# Controller.net
KiCad netlist of a schematic drawn in EAGLE
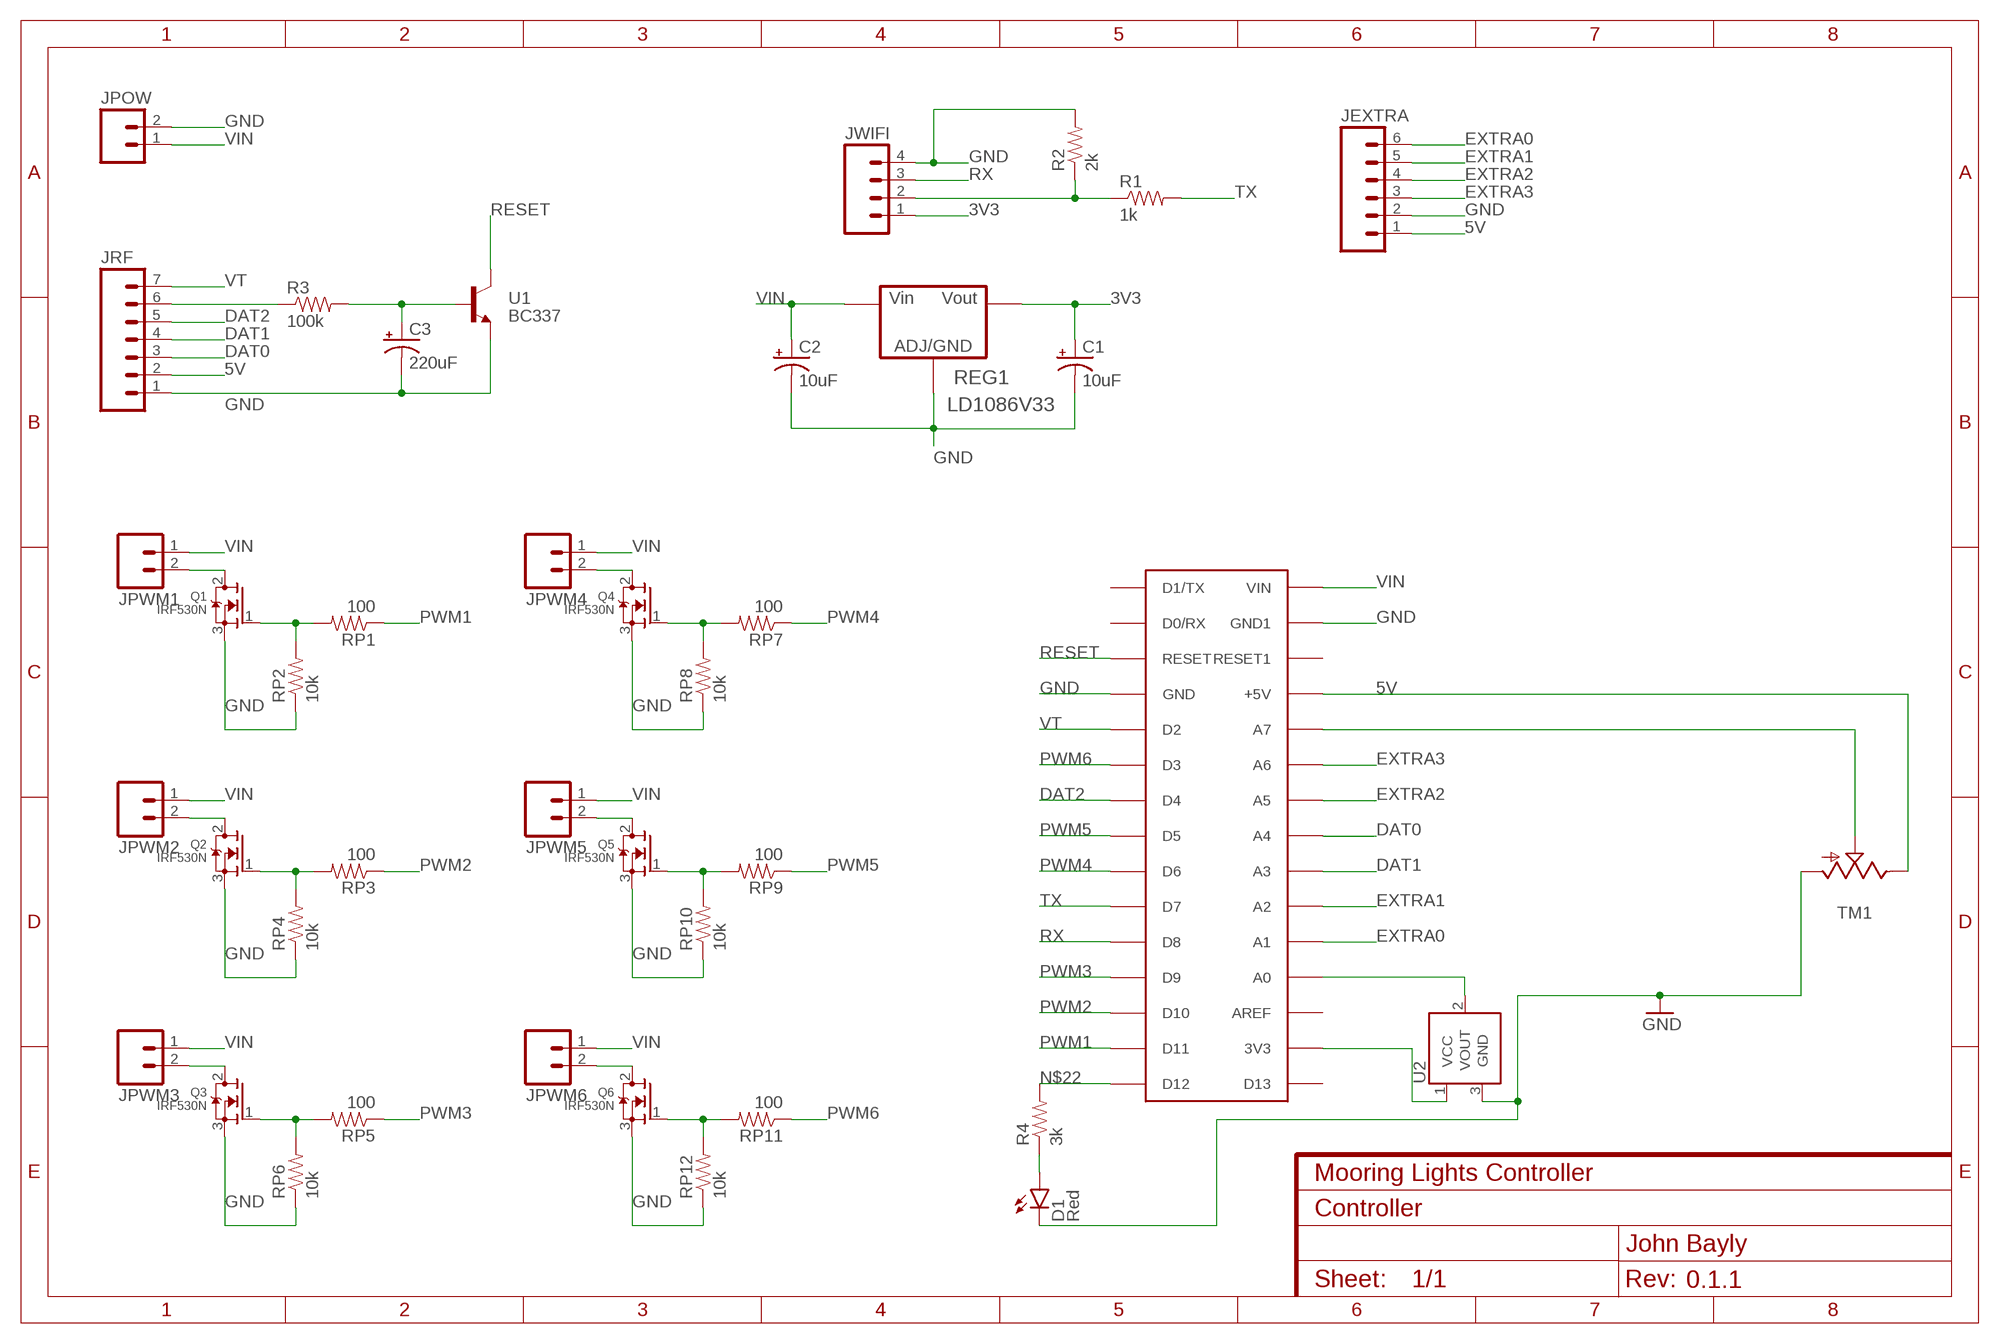
[diagram p0: schematic, sheet 1]

(export (version "E")
  (design (tool "Eeschema 10.0.6"))
  (components
    (comp (ref "C1")
      (value "10uF")
      (footprint "eagle-import:CPOL-RADIAL-10UF-25V")
      (libsource (lib "eagle-import") (part "10UF-25V-20%(PTH)"))
    )
    (comp (ref "C2")
      (value "10uF")
      (footprint "eagle-import:CPOL-RADIAL-10UF-25V")
      (libsource (lib "eagle-import") (part "10UF-25V-20%(PTH)"))
    )
    (comp (ref "C3")
      (value "220uF")
      (footprint "eagle-import:CPOL-RADIAL-100UF-25V")
      (libsource (lib "eagle-import") (part "100UF-25V-20%(PTH)"))
    )
    (comp (ref "D1")
      (value "Red")
      (footprint "eagle-import:LED5MM")
      (libsource (lib "eagle-import") (part "LED5MM"))
    )
    (comp (ref "JEXTRA")
      (value "M06SILK_FEMALE_PTH")
      (footprint "eagle-import:1X06")
      (libsource (lib "eagle-import") (part "M06SILK_FEMALE_PTH"))
    )
    (comp (ref "JPOW")
      (value "M025MM")
      (footprint "eagle-import:SCREWTERMINAL-5MM-2")
      (libsource (lib "eagle-import") (part "M025MM"))
    )
    (comp (ref "JPWM1")
      (value "M025MM")
      (footprint "eagle-import:SCREWTERMINAL-5MM-2")
      (libsource (lib "eagle-import") (part "M025MM"))
    )
    (comp (ref "JPWM2")
      (value "M025MM")
      (footprint "eagle-import:SCREWTERMINAL-5MM-2")
      (libsource (lib "eagle-import") (part "M025MM"))
    )
    (comp (ref "JPWM3")
      (value "M025MM")
      (footprint "eagle-import:SCREWTERMINAL-5MM-2")
      (libsource (lib "eagle-import") (part "M025MM"))
    )
    (comp (ref "JPWM4")
      (value "M025MM")
      (footprint "eagle-import:SCREWTERMINAL-5MM-2")
      (libsource (lib "eagle-import") (part "M025MM"))
    )
    (comp (ref "JPWM5")
      (value "M025MM")
      (footprint "eagle-import:SCREWTERMINAL-5MM-2")
      (libsource (lib "eagle-import") (part "M025MM"))
    )
    (comp (ref "JPWM6")
      (value "M025MM")
      (footprint "eagle-import:SCREWTERMINAL-5MM-2")
      (libsource (lib "eagle-import") (part "M025MM"))
    )
    (comp (ref "JRF")
      (value "M07")
      (footprint "eagle-import:1X07")
      (libsource (lib "eagle-import") (part "M07"))
    )
    (comp (ref "JWIFI")
      (value "M04PTH")
      (footprint "eagle-import:1X04")
      (libsource (lib "eagle-import") (part "M04PTH"))
    )
    (comp (ref "NANO")
      (value "ARDUINONANONO-MOUNT")
      (footprint "eagle-import:PDIP-32-NO-MOUNT")
      (libsource (lib "eagle-import") (part "ARDUINONANONO-MOUNT"))
    )
    (comp (ref "Q1")
      (value "IRF530N")
      (footprint "eagle-import:TO220V")
      (libsource (lib "eagle-import") (part "MOSFET-NGDS_TO220V"))
    )
    (comp (ref "Q2")
      (value "IRF530N")
      (footprint "eagle-import:TO220V")
      (libsource (lib "eagle-import") (part "MOSFET-NGDS_TO220V"))
    )
    (comp (ref "Q3")
      (value "IRF530N")
      (footprint "eagle-import:TO220V")
      (libsource (lib "eagle-import") (part "MOSFET-NGDS_TO220V"))
    )
    (comp (ref "Q4")
      (value "IRF530N")
      (footprint "eagle-import:TO220V")
      (libsource (lib "eagle-import") (part "MOSFET-NGDS_TO220V"))
    )
    (comp (ref "Q5")
      (value "IRF530N")
      (footprint "eagle-import:TO220V")
      (libsource (lib "eagle-import") (part "MOSFET-NGDS_TO220V"))
    )
    (comp (ref "Q6")
      (value "IRF530N")
      (footprint "eagle-import:TO220V")
      (libsource (lib "eagle-import") (part "MOSFET-NGDS_TO220V"))
    )
    (comp (ref "R1")
      (value "1k")
      (footprint "eagle-import:AXIAL-0.4")
      (libsource (lib "eagle-import") (part "RESISTORPTH-1/4W"))
    )
    (comp (ref "R2")
      (value "2k")
      (footprint "eagle-import:AXIAL-0.4")
      (libsource (lib "eagle-import") (part "RESISTORPTH-1/4W"))
    )
    (comp (ref "R3")
      (value "100k")
      (footprint "eagle-import:AXIAL-0.4")
      (libsource (lib "eagle-import") (part "RESISTORPTH-1/4W"))
    )
    (comp (ref "R4")
      (value "3k")
      (footprint "eagle-import:AXIAL-0.4")
      (libsource (lib "eagle-import") (part "RESISTORPTH-1/4W"))
    )
    (comp (ref "REG1")
      (value "LD1086V33")
      (footprint "eagle-import:TO254P482X1024X3124-3P")
      (libsource (lib "eagle-import") (part "LD1086V33"))
    )
    (comp (ref "RP1")
      (value "100")
      (footprint "eagle-import:AXIAL-0.4")
      (libsource (lib "eagle-import") (part "RESISTORPTH-1/4W"))
    )
    (comp (ref "RP2")
      (value "10k")
      (footprint "eagle-import:AXIAL-0.4")
      (libsource (lib "eagle-import") (part "RESISTORPTH-1/4W"))
    )
    (comp (ref "RP3")
      (value "100")
      (footprint "eagle-import:AXIAL-0.4")
      (libsource (lib "eagle-import") (part "RESISTORPTH-1/4W"))
    )
    (comp (ref "RP4")
      (value "10k")
      (footprint "eagle-import:AXIAL-0.4")
      (libsource (lib "eagle-import") (part "RESISTORPTH-1/4W"))
    )
    (comp (ref "RP5")
      (value "100")
      (footprint "eagle-import:AXIAL-0.4")
      (libsource (lib "eagle-import") (part "RESISTORPTH-1/4W"))
    )
    (comp (ref "RP6")
      (value "10k")
      (footprint "eagle-import:AXIAL-0.4")
      (libsource (lib "eagle-import") (part "RESISTORPTH-1/4W"))
    )
    (comp (ref "RP7")
      (value "100")
      (footprint "eagle-import:AXIAL-0.4")
      (libsource (lib "eagle-import") (part "RESISTORPTH-1/4W"))
    )
    (comp (ref "RP8")
      (value "10k")
      (footprint "eagle-import:AXIAL-0.4")
      (libsource (lib "eagle-import") (part "RESISTORPTH-1/4W"))
    )
    (comp (ref "RP9")
      (value "100")
      (footprint "eagle-import:AXIAL-0.4")
      (libsource (lib "eagle-import") (part "RESISTORPTH-1/4W"))
    )
    (comp (ref "RP10")
      (value "10k")
      (footprint "eagle-import:AXIAL-0.4")
      (libsource (lib "eagle-import") (part "RESISTORPTH-1/4W"))
    )
    (comp (ref "RP11")
      (value "100")
      (footprint "eagle-import:AXIAL-0.4")
      (libsource (lib "eagle-import") (part "RESISTORPTH-1/4W"))
    )
    (comp (ref "RP12")
      (value "10k")
      (footprint "eagle-import:AXIAL-0.4")
      (libsource (lib "eagle-import") (part "RESISTORPTH-1/4W"))
    )
    (comp (ref "TM1")
      (value "TRIM")
      (footprint "eagle-import:6MM")
      (libsource (lib "eagle-import") (part "TRIM"))
    )
    (comp (ref "U1")
      (value "BC337")
      (footprint "eagle-import:TO-92")
      (libsource (lib "eagle-import") (part "TRANSISTOR_NPN_2PTH"))
    )
    (comp (ref "U2")
      (value "TMP36GT9")
      (footprint "eagle-import:TO-92")
      (libsource (lib "eagle-import") (part "TMP36GT9"))
    )
  )
  (nets
    (net (code "1") (name "/3V3") (class "Default")
      (node (ref "C1") (pin "1") (pinfunction "+_1") (pintype "passive"))
      (node (ref "JWIFI") (pin "1") (pinfunction "1_1") (pintype "passive"))
      (node (ref "REG1") (pin "2") (pinfunction "VOUT_2") (pintype "output"))
    )
    (net (code "2") (name "/5V") (class "Default")
      (node (ref "JEXTRA") (pin "1") (pinfunction "1_1") (pintype "passive"))
      (node (ref "JRF") (pin "2") (pinfunction "2_2") (pintype "passive"))
      (node (ref "NANO") (pin "+5V") (pinfunction "+5V_+5V") (pintype "bidirectional"))
      (node (ref "TM1") (pin "E") (pinfunction "E_E") (pintype "passive"))
    )
    (net (code "3") (name "/DAT0") (class "Default")
      (node (ref "JRF") (pin "3") (pinfunction "3_3") (pintype "passive"))
      (node (ref "NANO") (pin "A3") (pinfunction "A4_A3") (pintype "bidirectional"))
    )
    (net (code "4") (name "/DAT1") (class "Default")
      (node (ref "JRF") (pin "4") (pinfunction "4_4") (pintype "passive"))
      (node (ref "NANO") (pin "A4") (pinfunction "A3_A4") (pintype "bidirectional"))
    )
    (net (code "5") (name "/DAT2") (class "Default")
      (node (ref "JRF") (pin "5") (pinfunction "5_5") (pintype "passive"))
      (node (ref "NANO") (pin "D4") (pinfunction "D4_D4") (pintype "bidirectional"))
    )
    (net (code "6") (name "/EXTRA0") (class "Default")
      (node (ref "JEXTRA") (pin "6") (pinfunction "6_6") (pintype "passive"))
      (node (ref "NANO") (pin "A6") (pinfunction "A1_A6") (pintype "bidirectional"))
    )
    (net (code "7") (name "/EXTRA1") (class "Default")
      (node (ref "JEXTRA") (pin "5") (pinfunction "5_5") (pintype "passive"))
      (node (ref "NANO") (pin "A5") (pinfunction "A2_A5") (pintype "bidirectional"))
    )
    (net (code "8") (name "/EXTRA2") (class "Default")
      (node (ref "JEXTRA") (pin "4") (pinfunction "4_4") (pintype "passive"))
      (node (ref "NANO") (pin "A2") (pinfunction "A5_A2") (pintype "bidirectional"))
    )
    (net (code "9") (name "/EXTRA3") (class "Default")
      (node (ref "JEXTRA") (pin "3") (pinfunction "3_3") (pintype "passive"))
      (node (ref "NANO") (pin "A1") (pinfunction "A6_A1") (pintype "bidirectional"))
    )
    (net (code "10") (name "/N$22") (class "Default")
      (node (ref "NANO") (pin "D12") (pinfunction "D12_D12") (pintype "bidirectional"))
      (node (ref "R4") (pin "P$2") (pinfunction "2_P$2") (pintype "passive"))
    )
    (net (code "11") (name "/PWM1") (class "Default")
      (node (ref "NANO") (pin "D11") (pinfunction "D11_D11") (pintype "bidirectional"))
      (node (ref "RP1") (pin "P$1") (pinfunction "1_P$1") (pintype "passive"))
    )
    (net (code "12") (name "/PWM2") (class "Default")
      (node (ref "NANO") (pin "D10") (pinfunction "D10_D10") (pintype "bidirectional"))
      (node (ref "RP3") (pin "P$1") (pinfunction "1_P$1") (pintype "passive"))
    )
    (net (code "13") (name "/PWM3") (class "Default")
      (node (ref "NANO") (pin "D9") (pinfunction "D9_D9") (pintype "bidirectional"))
      (node (ref "RP5") (pin "P$1") (pinfunction "1_P$1") (pintype "passive"))
    )
    (net (code "14") (name "/PWM4") (class "Default")
      (node (ref "NANO") (pin "D6") (pinfunction "D6_D6") (pintype "bidirectional"))
      (node (ref "RP7") (pin "P$1") (pinfunction "1_P$1") (pintype "passive"))
    )
    (net (code "15") (name "/PWM5") (class "Default")
      (node (ref "NANO") (pin "D5") (pinfunction "D5_D5") (pintype "bidirectional"))
      (node (ref "RP9") (pin "P$1") (pinfunction "1_P$1") (pintype "passive"))
    )
    (net (code "16") (name "/PWM6") (class "Default")
      (node (ref "NANO") (pin "D3") (pinfunction "D3_D3") (pintype "bidirectional"))
      (node (ref "RP11") (pin "P$1") (pinfunction "1_P$1") (pintype "passive"))
    )
    (net (code "17") (name "/RESET") (class "Default")
      (node (ref "NANO") (pin "RESET") (pinfunction "RESET_RESET") (pintype "bidirectional"))
      (node (ref "U1") (pin "1") (pinfunction "C_1") (pintype "passive"))
    )
    (net (code "18") (name "/RX") (class "Default")
      (node (ref "JWIFI") (pin "3") (pinfunction "3_3") (pintype "passive"))
      (node (ref "NANO") (pin "D8") (pinfunction "D8_D8") (pintype "bidirectional"))
    )
    (net (code "19") (name "/TX") (class "Default")
      (node (ref "NANO") (pin "D7") (pinfunction "D7_D7") (pintype "bidirectional"))
      (node (ref "R1") (pin "P$2") (pinfunction "2_P$2") (pintype "passive"))
    )
    (net (code "20") (name "/VIN") (class "Default")
      (node (ref "C2") (pin "1") (pinfunction "+_1") (pintype "passive"))
      (node (ref "JPOW") (pin "1") (pinfunction "1_1") (pintype "passive"))
      (node (ref "JPWM1") (pin "1") (pinfunction "1_1") (pintype "passive"))
      (node (ref "JPWM2") (pin "1") (pinfunction "1_1") (pintype "passive"))
      (node (ref "JPWM3") (pin "1") (pinfunction "1_1") (pintype "passive"))
      (node (ref "JPWM4") (pin "1") (pinfunction "1_1") (pintype "passive"))
      (node (ref "JPWM5") (pin "1") (pinfunction "1_1") (pintype "passive"))
      (node (ref "JPWM6") (pin "1") (pinfunction "1_1") (pintype "passive"))
      (node (ref "NANO") (pin "VIN") (pinfunction "VIN_VIN") (pintype "bidirectional"))
      (node (ref "REG1") (pin "3") (pinfunction "VIN_3") (pintype "input"))
    )
    (net (code "21") (name "/VT") (class "Default")
      (node (ref "JRF") (pin "7") (pinfunction "7_7") (pintype "passive"))
      (node (ref "NANO") (pin "D2") (pinfunction "D2_D2") (pintype "bidirectional"))
    )
    (net (code "22") (name "GND") (class "Default")
      (node (ref "C1") (pin "2") (pinfunction "-_2") (pintype "passive"))
      (node (ref "C2") (pin "2") (pinfunction "-_2") (pintype "passive"))
      (node (ref "C3") (pin "2") (pinfunction "-_2") (pintype "passive"))
      (node (ref "D1") (pin "K") (pinfunction "C_K") (pintype "passive"))
      (node (ref "JEXTRA") (pin "2") (pinfunction "2_2") (pintype "passive"))
      (node (ref "JPOW") (pin "2") (pinfunction "2_2") (pintype "passive"))
      (node (ref "JRF") (pin "1") (pinfunction "1_1") (pintype "passive"))
      (node (ref "JWIFI") (pin "4") (pinfunction "4_4") (pintype "passive"))
      (node (ref "NANO") (pin "GND") (pinfunction "GND_GND") (pintype "bidirectional"))
      (node (ref "NANO") (pin "GND1") (pinfunction "GND1_GND1") (pintype "bidirectional"))
      (node (ref "Q1") (pin "3") (pinfunction "S_3") (pintype "bidirectional"))
      (node (ref "Q2") (pin "3") (pinfunction "S_3") (pintype "bidirectional"))
      (node (ref "Q3") (pin "3") (pinfunction "S_3") (pintype "bidirectional"))
      (node (ref "Q4") (pin "3") (pinfunction "S_3") (pintype "bidirectional"))
      (node (ref "Q5") (pin "3") (pinfunction "S_3") (pintype "bidirectional"))
      (node (ref "Q6") (pin "3") (pinfunction "S_3") (pintype "bidirectional"))
      (node (ref "R2") (pin "P$2") (pinfunction "2_P$2") (pintype "passive"))
      (node (ref "REG1") (pin "1") (pinfunction "ADJ/GND_1") (pintype "passive"))
      (node (ref "RP10") (pin "P$1") (pinfunction "1_P$1") (pintype "passive"))
      (node (ref "RP12") (pin "P$1") (pinfunction "1_P$1") (pintype "passive"))
      (node (ref "RP2") (pin "P$1") (pinfunction "1_P$1") (pintype "passive"))
      (node (ref "RP4") (pin "P$1") (pinfunction "1_P$1") (pintype "passive"))
      (node (ref "RP6") (pin "P$1") (pinfunction "1_P$1") (pintype "passive"))
      (node (ref "RP8") (pin "P$1") (pinfunction "1_P$1") (pintype "passive"))
      (node (ref "TM1") (pin "A") (pinfunction "A_A") (pintype "passive"))
      (node (ref "U1") (pin "3") (pinfunction "E_3") (pintype "passive"))
      (node (ref "U2") (pin "3") (pinfunction "GND_3") (pintype "bidirectional"))
    )
    (net (code "23") (name "Net-(C3-+)") (class "Default")
      (node (ref "C3") (pin "1") (pinfunction "+_1") (pintype "passive"))
      (node (ref "R3") (pin "P$2") (pinfunction "2_P$2") (pintype "passive"))
      (node (ref "U1") (pin "2") (pinfunction "B_2") (pintype "passive"))
    )
    (net (code "24") (name "Net-(NANO-A0)") (class "Default")
      (node (ref "NANO") (pin "A7") (pinfunction "A0_A7") (pintype "bidirectional"))
      (node (ref "U2") (pin "2") (pinfunction "VOUT_2") (pintype "bidirectional"))
    )
    (net (code "25") (name "Net-(NANO-A7)") (class "Default")
      (node (ref "NANO") (pin "A0") (pinfunction "A7_A0") (pintype "bidirectional"))
      (node (ref "TM1") (pin "S") (pinfunction "S_S") (pintype "passive"))
    )
    (net (code "26") (name "Net-(Q1-D)") (class "Default")
      (node (ref "JPWM1") (pin "2") (pinfunction "2_2") (pintype "passive"))
      (node (ref "Q1") (pin "2") (pinfunction "D_2") (pintype "bidirectional"))
    )
    (net (code "27") (name "Net-(Q1-G)") (class "Default")
      (node (ref "Q1") (pin "1") (pinfunction "G_1") (pintype "bidirectional"))
      (node (ref "RP1") (pin "P$2") (pinfunction "2_P$2") (pintype "passive"))
      (node (ref "RP2") (pin "P$2") (pinfunction "2_P$2") (pintype "passive"))
    )
    (net (code "28") (name "Net-(Q2-D)") (class "Default")
      (node (ref "JPWM2") (pin "2") (pinfunction "2_2") (pintype "passive"))
      (node (ref "Q2") (pin "2") (pinfunction "D_2") (pintype "bidirectional"))
    )
    (net (code "29") (name "Net-(Q2-G)") (class "Default")
      (node (ref "Q2") (pin "1") (pinfunction "G_1") (pintype "bidirectional"))
      (node (ref "RP3") (pin "P$2") (pinfunction "2_P$2") (pintype "passive"))
      (node (ref "RP4") (pin "P$2") (pinfunction "2_P$2") (pintype "passive"))
    )
    (net (code "30") (name "Net-(Q3-D)") (class "Default")
      (node (ref "JPWM3") (pin "2") (pinfunction "2_2") (pintype "passive"))
      (node (ref "Q3") (pin "2") (pinfunction "D_2") (pintype "bidirectional"))
    )
    (net (code "31") (name "Net-(Q3-G)") (class "Default")
      (node (ref "Q3") (pin "1") (pinfunction "G_1") (pintype "bidirectional"))
      (node (ref "RP5") (pin "P$2") (pinfunction "2_P$2") (pintype "passive"))
      (node (ref "RP6") (pin "P$2") (pinfunction "2_P$2") (pintype "passive"))
    )
    (net (code "32") (name "Net-(Q4-D)") (class "Default")
      (node (ref "JPWM4") (pin "2") (pinfunction "2_2") (pintype "passive"))
      (node (ref "Q4") (pin "2") (pinfunction "D_2") (pintype "bidirectional"))
    )
    (net (code "33") (name "Net-(Q4-G)") (class "Default")
      (node (ref "Q4") (pin "1") (pinfunction "G_1") (pintype "bidirectional"))
      (node (ref "RP7") (pin "P$2") (pinfunction "2_P$2") (pintype "passive"))
      (node (ref "RP8") (pin "P$2") (pinfunction "2_P$2") (pintype "passive"))
    )
    (net (code "34") (name "Net-(Q5-D)") (class "Default")
      (node (ref "JPWM5") (pin "2") (pinfunction "2_2") (pintype "passive"))
      (node (ref "Q5") (pin "2") (pinfunction "D_2") (pintype "bidirectional"))
    )
    (net (code "35") (name "Net-(Q5-G)") (class "Default")
      (node (ref "Q5") (pin "1") (pinfunction "G_1") (pintype "bidirectional"))
      (node (ref "RP10") (pin "P$2") (pinfunction "2_P$2") (pintype "passive"))
      (node (ref "RP9") (pin "P$2") (pinfunction "2_P$2") (pintype "passive"))
    )
    (net (code "36") (name "Net-(Q6-D)") (class "Default")
      (node (ref "JPWM6") (pin "2") (pinfunction "2_2") (pintype "passive"))
      (node (ref "Q6") (pin "2") (pinfunction "D_2") (pintype "bidirectional"))
    )
    (net (code "37") (name "Net-(Q6-G)") (class "Default")
      (node (ref "Q6") (pin "1") (pinfunction "G_1") (pintype "bidirectional"))
      (node (ref "RP11") (pin "P$2") (pinfunction "2_P$2") (pintype "passive"))
      (node (ref "RP12") (pin "P$2") (pinfunction "2_P$2") (pintype "passive"))
    )
    (net (code "38") (name "Net-(R1-1)") (class "Default")
      (node (ref "JWIFI") (pin "2") (pinfunction "2_2") (pintype "passive"))
      (node (ref "R1") (pin "P$1") (pinfunction "1_P$1") (pintype "passive"))
      (node (ref "R2") (pin "P$1") (pinfunction "1_P$1") (pintype "passive"))
    )
    (net (code "39") (name "Net-(R3-1)") (class "Default")
      (node (ref "JRF") (pin "6") (pinfunction "6_6") (pintype "passive"))
      (node (ref "R3") (pin "P$1") (pinfunction "1_P$1") (pintype "passive"))
    )
    (net (code "40") (name "Net-(R4-1)") (class "Default")
      (node (ref "D1") (pin "A") (pinfunction "A_A") (pintype "passive"))
      (node (ref "R4") (pin "P$1") (pinfunction "1_P$1") (pintype "passive"))
    )
    (net (code "41") (name "Net-(U2-VCC)") (class "Default")
      (node (ref "NANO") (pin "3V3") (pinfunction "3V3_3V3") (pintype "bidirectional"))
      (node (ref "U2") (pin "1") (pinfunction "VCC_1") (pintype "bidirectional"))
    )
    (net (code "42") (name "unconnected-(NANO-PadAREF)") (class "Default")
      (node (ref "NANO") (pin "AREF") (pinfunction "AREF_AREF") (pintype "bidirectional"))
    )
    (net (code "43") (name "unconnected-(NANO-PadD0{slash}RX)") (class "Default")
      (node (ref "NANO") (pin "D0/RX") (pinfunction "D0/RX_D0/RX") (pintype "bidirectional"))
    )
    (net (code "44") (name "unconnected-(NANO-PadD1{slash}TX)") (class "Default")
      (node (ref "NANO") (pin "D1/TX") (pinfunction "D1/TX_D1/TX") (pintype "bidirectional"))
    )
    (net (code "45") (name "unconnected-(NANO-PadD13)") (class "Default")
      (node (ref "NANO") (pin "D13") (pinfunction "D13_D13") (pintype "bidirectional"))
    )
    (net (code "46") (name "unconnected-(NANO-PadRESET1)") (class "Default")
      (node (ref "NANO") (pin "RESET1") (pinfunction "RESET1_RESET1") (pintype "bidirectional"))
    )
  )
)
